# bldc_shield_eagle_layout.net
KiCad netlist of a schematic drawn in EAGLE
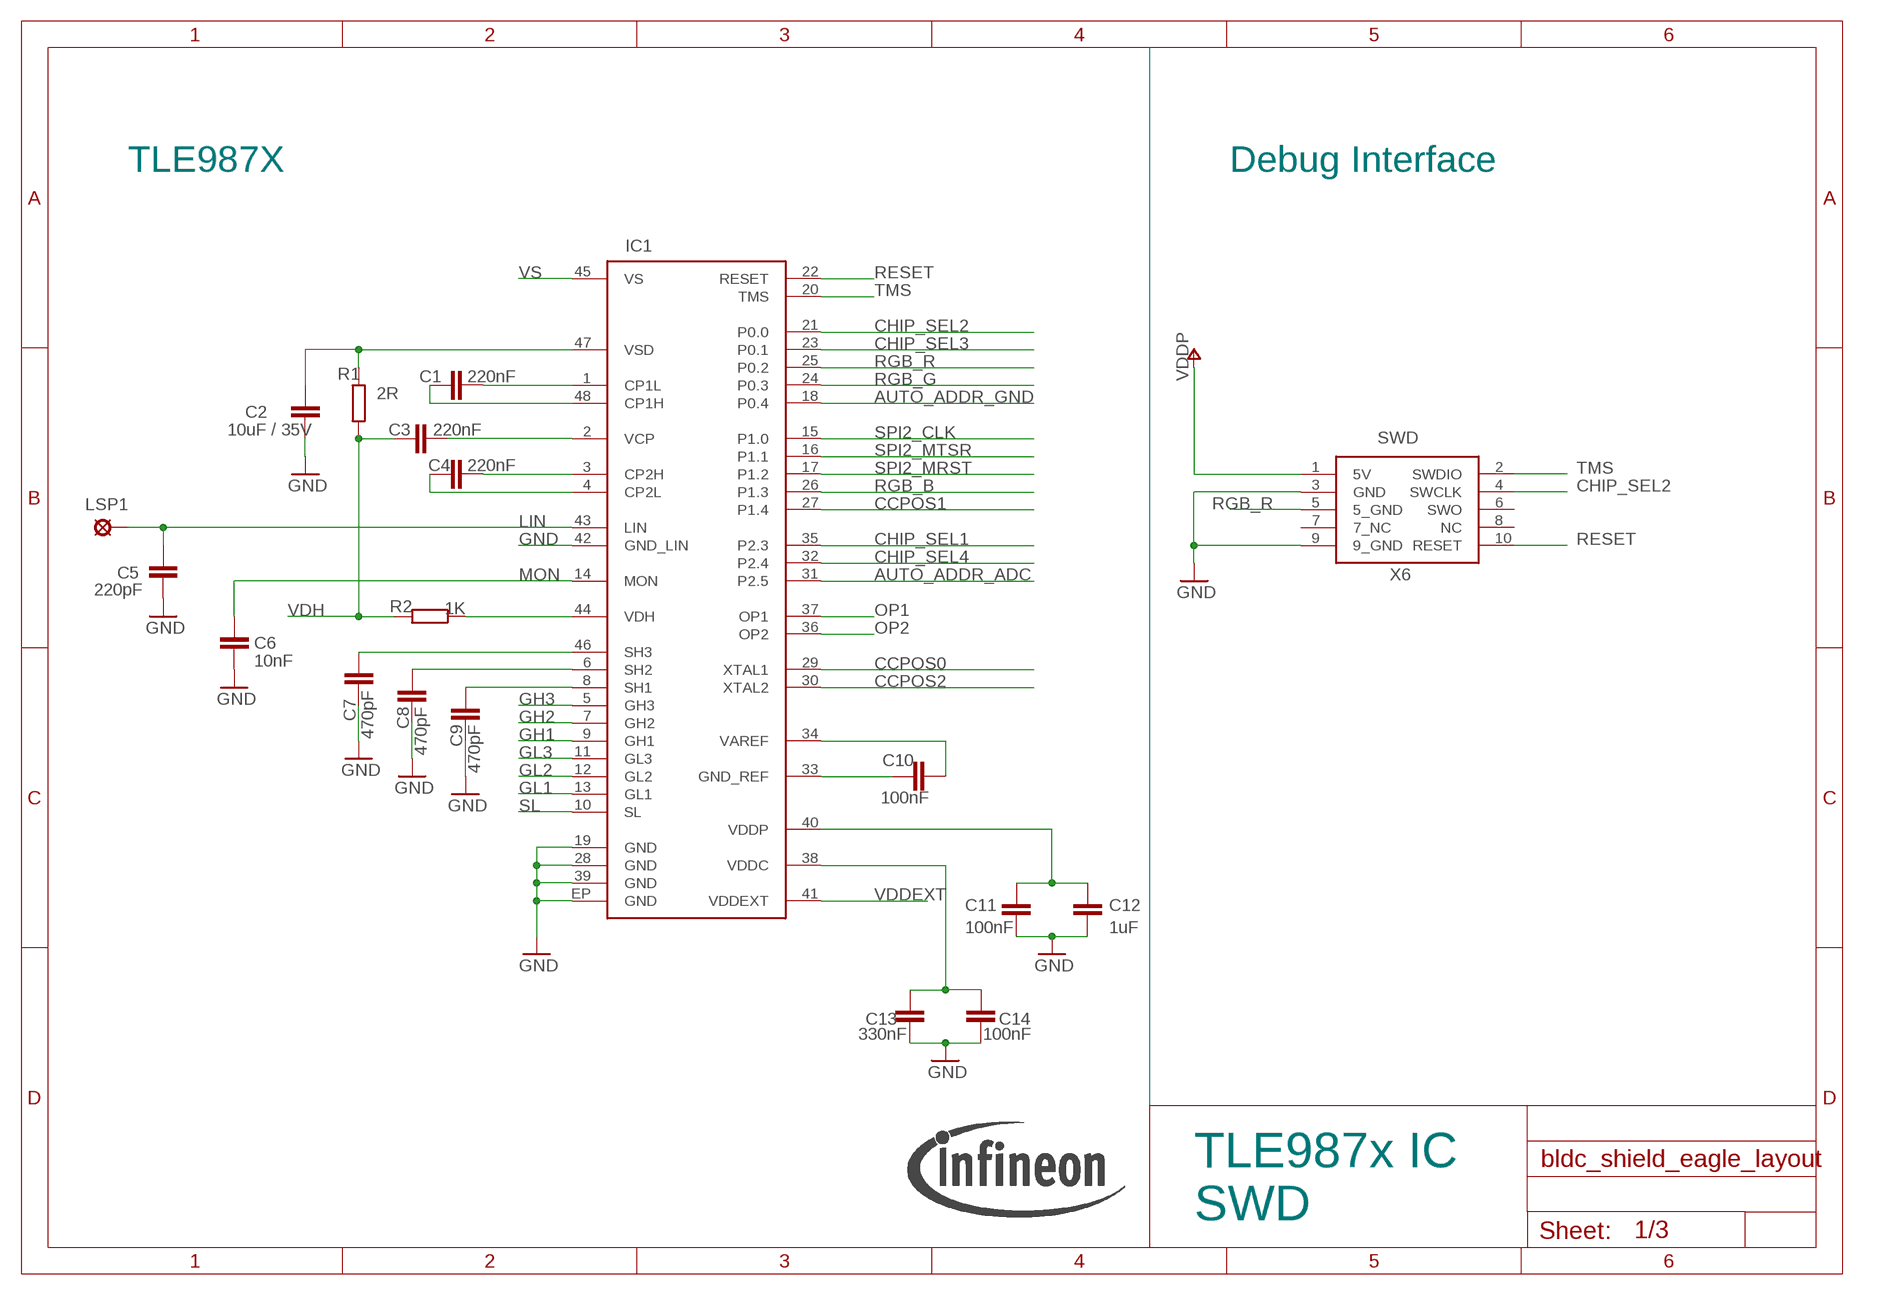
[diagram p0: schematic, sheet 1]
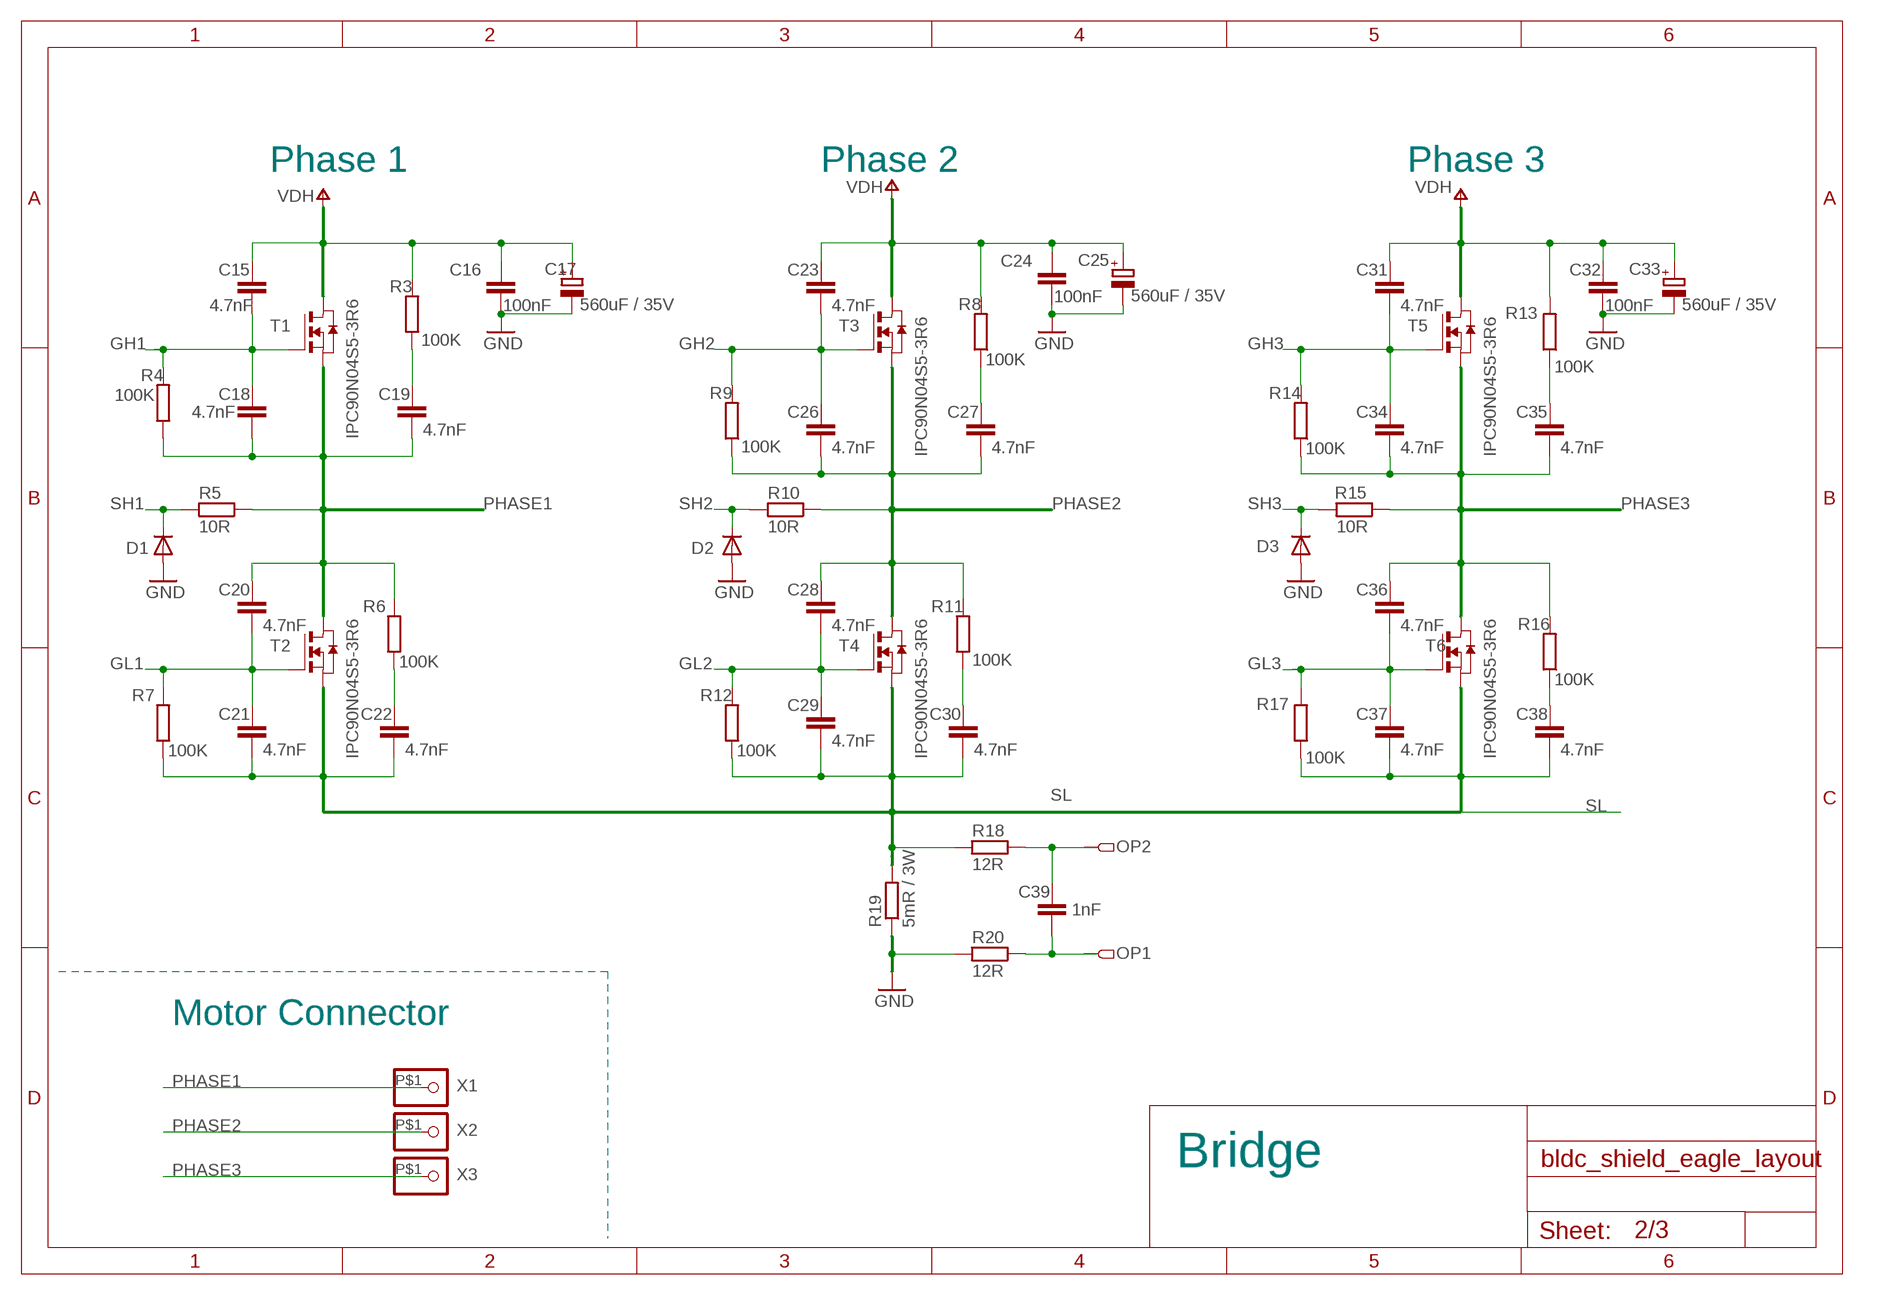
[diagram p1: schematic, sheet 2]
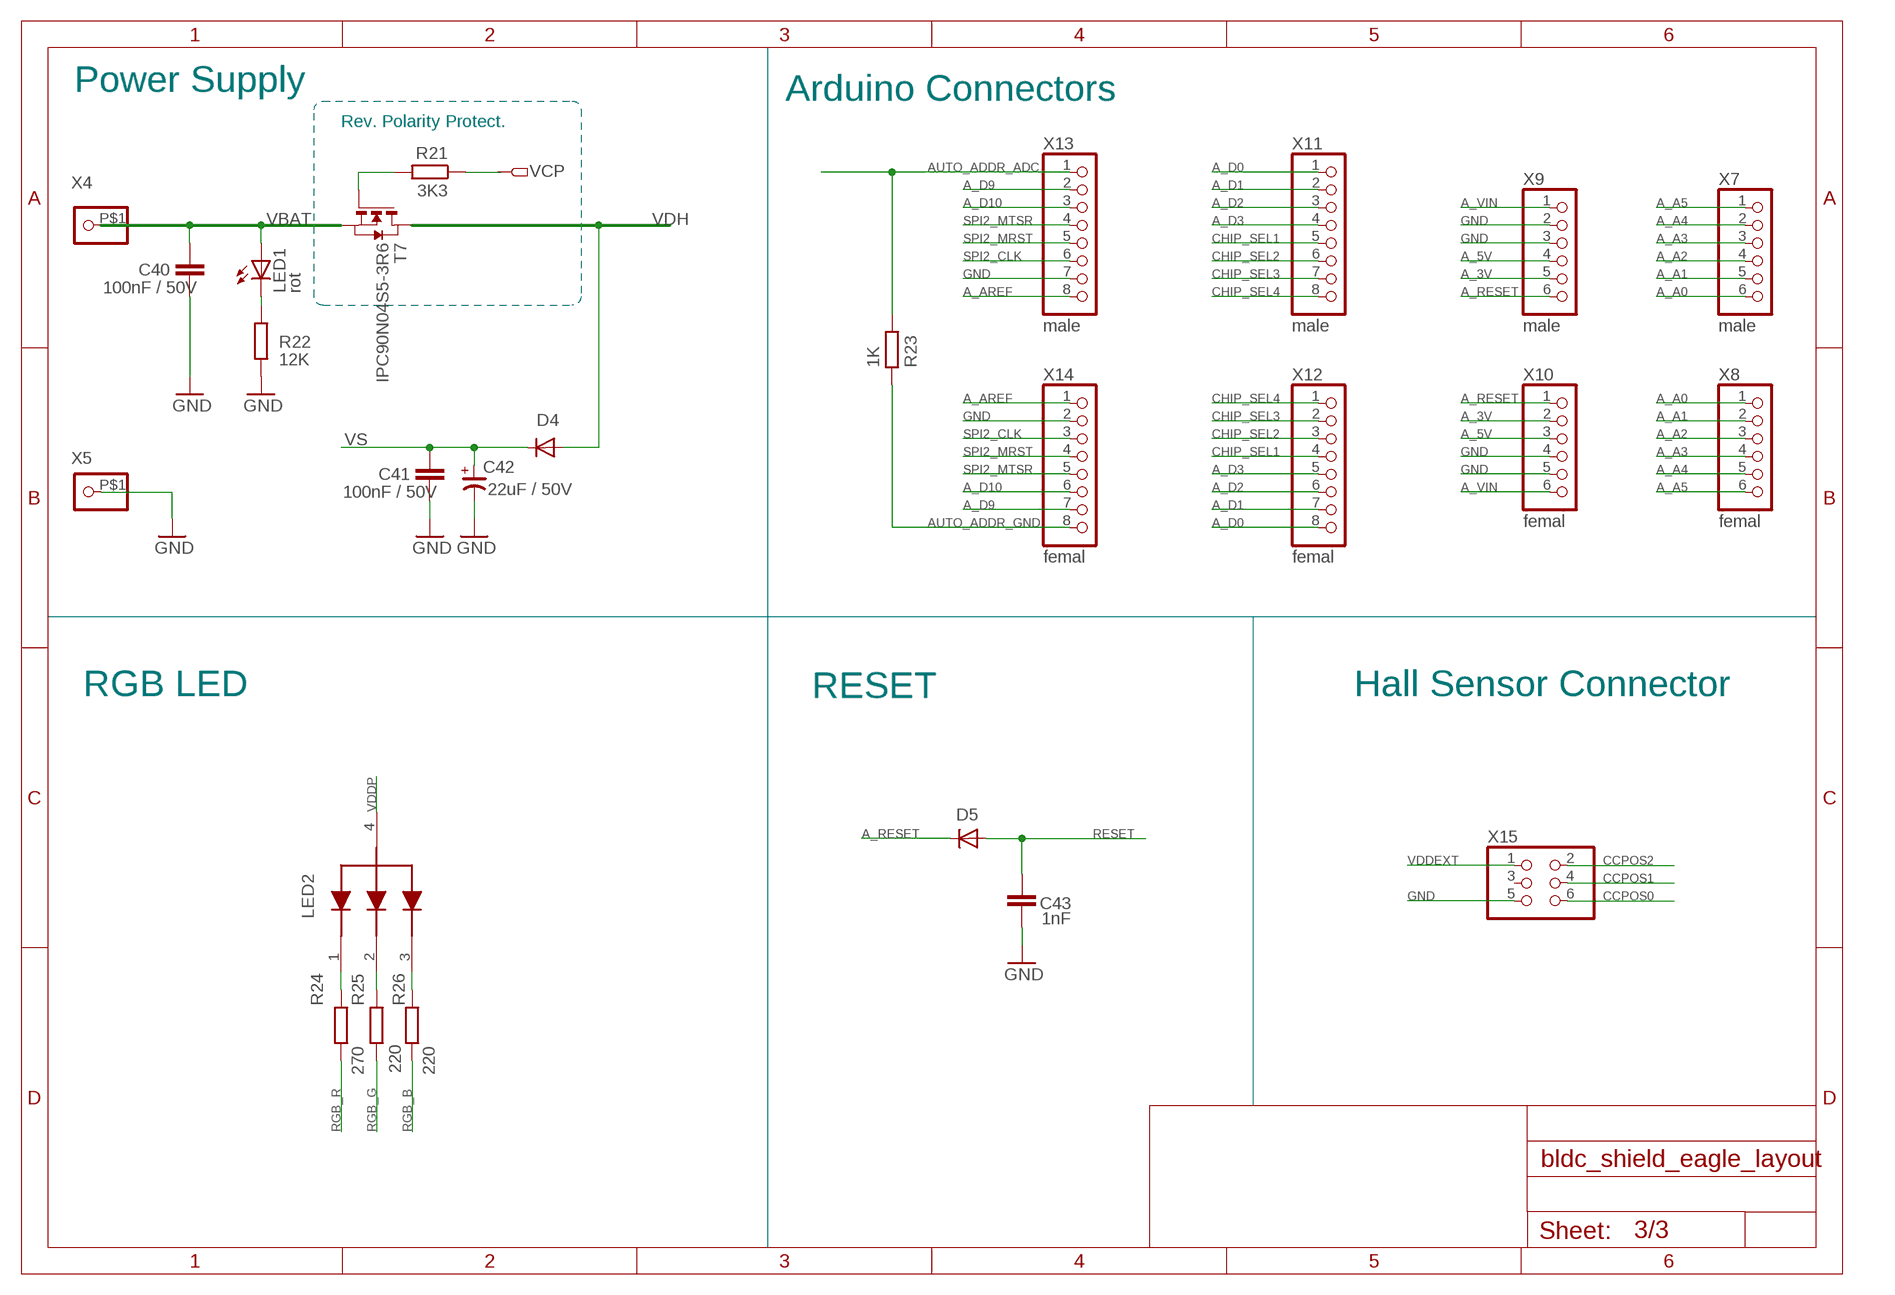
[diagram p2: schematic, sheet 3]

(export (version "E")
  (design (tool "Eeschema 10.0.6"))
  (components
    (comp (ref "C15")
      (value "4.7nF")
      (footprint "eagle-import:C0603")
      (libsource (lib "eagle-import") (part "C-EUC0603"))
    )
    (comp (ref "C16")
      (value "100nF")
      (footprint "eagle-import:C0603")
      (libsource (lib "eagle-import") (part "C-EUC0603"))
    )
    (comp (ref "C17")
      (value "560uF / 35V")
      (footprint "eagle-import:153CLV-1014")
      (libsource (lib "eagle-import") (part "CPOL-EU153CLV-1014"))
    )
    (comp (ref "C18")
      (value "4.7nF")
      (footprint "eagle-import:C0603")
      (libsource (lib "eagle-import") (part "C-EUC0603"))
    )
    (comp (ref "C19")
      (value "4.7nF")
      (footprint "eagle-import:C0603")
      (libsource (lib "eagle-import") (part "C-EUC0603"))
    )
    (comp (ref "C20")
      (value "4.7nF")
      (footprint "eagle-import:C0603")
      (libsource (lib "eagle-import") (part "C-EUC0603"))
    )
    (comp (ref "C21")
      (value "4.7nF")
      (footprint "eagle-import:C0603")
      (libsource (lib "eagle-import") (part "C-EUC0603"))
    )
    (comp (ref "C22")
      (value "4.7nF")
      (footprint "eagle-import:C0603")
      (libsource (lib "eagle-import") (part "C-EUC0603"))
    )
    (comp (ref "C23")
      (value "4.7nF")
      (footprint "eagle-import:C0603")
      (libsource (lib "eagle-import") (part "C-EUC0603"))
    )
    (comp (ref "C24")
      (value "100nF")
      (footprint "eagle-import:C0603")
      (libsource (lib "eagle-import") (part "C-EUC0603"))
    )
    (comp (ref "C25")
      (value "560uF / 35V")
      (footprint "eagle-import:153CLV-1014")
      (libsource (lib "eagle-import") (part "CPOL-EU153CLV-1014"))
    )
    (comp (ref "C26")
      (value "4.7nF")
      (footprint "eagle-import:C0603")
      (libsource (lib "eagle-import") (part "C-EUC0603"))
    )
    (comp (ref "C27")
      (value "4.7nF")
      (footprint "eagle-import:C0603")
      (libsource (lib "eagle-import") (part "C-EUC0603"))
    )
    (comp (ref "C28")
      (value "4.7nF")
      (footprint "eagle-import:C0603")
      (libsource (lib "eagle-import") (part "C-EUC0603"))
    )
    (comp (ref "C29")
      (value "4.7nF")
      (footprint "eagle-import:C0603")
      (libsource (lib "eagle-import") (part "C-EUC0603"))
    )
    (comp (ref "C30")
      (value "4.7nF")
      (footprint "eagle-import:C0603")
      (libsource (lib "eagle-import") (part "C-EUC0603"))
    )
    (comp (ref "C31")
      (value "4.7nF")
      (footprint "eagle-import:C0603")
      (libsource (lib "eagle-import") (part "C-EUC0603"))
    )
    (comp (ref "C32")
      (value "100nF")
      (footprint "eagle-import:C0603")
      (libsource (lib "eagle-import") (part "C-EUC0603"))
    )
    (comp (ref "C33")
      (value "560uF / 35V")
      (footprint "eagle-import:153CLV-1014")
      (libsource (lib "eagle-import") (part "CPOL-EU153CLV-1014"))
    )
    (comp (ref "C34")
      (value "4.7nF")
      (footprint "eagle-import:C0603")
      (libsource (lib "eagle-import") (part "C-EUC0603"))
    )
    (comp (ref "C35")
      (value "4.7nF")
      (footprint "eagle-import:C0603")
      (libsource (lib "eagle-import") (part "C-EUC0603"))
    )
    (comp (ref "C36")
      (value "4.7nF")
      (footprint "eagle-import:C0603")
      (libsource (lib "eagle-import") (part "C-EUC0603"))
    )
    (comp (ref "C37")
      (value "4.7nF")
      (footprint "eagle-import:C0603")
      (libsource (lib "eagle-import") (part "C-EUC0603"))
    )
    (comp (ref "C38")
      (value "4.7nF")
      (footprint "eagle-import:C0603")
      (libsource (lib "eagle-import") (part "C-EUC0603"))
    )
    (comp (ref "C39")
      (value "1nF")
      (footprint "eagle-import:C0603")
      (libsource (lib "eagle-import") (part "C-EUC0603"))
    )
    (comp (ref "D1")
      (value "DIODE-SOD323-W")
      (footprint "eagle-import:SOD323-W")
      (libsource (lib "eagle-import") (part "DIODE-SOD323-W"))
    )
    (comp (ref "D2")
      (value "DIODE-SOD323-W")
      (footprint "eagle-import:SOD323-W")
      (libsource (lib "eagle-import") (part "DIODE-SOD323-W"))
    )
    (comp (ref "D3")
      (value "DIODE-SOD323-W")
      (footprint "eagle-import:SOD323-W")
      (libsource (lib "eagle-import") (part "DIODE-SOD323-W"))
    )
    (comp (ref "R3")
      (value "100K")
      (footprint "eagle-import:R0603")
      (libsource (lib "eagle-import") (part "R-EU_R0603"))
    )
    (comp (ref "R4")
      (value "100K")
      (footprint "eagle-import:R0603")
      (libsource (lib "eagle-import") (part "R-EU_R0603"))
    )
    (comp (ref "R5")
      (value "10R")
      (footprint "eagle-import:R0603")
      (libsource (lib "eagle-import") (part "R-EU_R0603"))
    )
    (comp (ref "R6")
      (value "100K")
      (footprint "eagle-import:R0603")
      (libsource (lib "eagle-import") (part "R-EU_R0603"))
    )
    (comp (ref "R7")
      (value "100K")
      (footprint "eagle-import:R0603")
      (libsource (lib "eagle-import") (part "R-EU_R0603"))
    )
    (comp (ref "R8")
      (value "100K")
      (footprint "eagle-import:R0603")
      (libsource (lib "eagle-import") (part "R-EU_R0603"))
    )
    (comp (ref "R9")
      (value "100K")
      (footprint "eagle-import:R0603")
      (libsource (lib "eagle-import") (part "R-EU_R0603"))
    )
    (comp (ref "R10")
      (value "10R")
      (footprint "eagle-import:R0603")
      (libsource (lib "eagle-import") (part "R-EU_R0603"))
    )
    (comp (ref "R11")
      (value "100K")
      (footprint "eagle-import:R0603")
      (libsource (lib "eagle-import") (part "R-EU_R0603"))
    )
    (comp (ref "R12")
      (value "100K")
      (footprint "eagle-import:R0603")
      (libsource (lib "eagle-import") (part "R-EU_R0603"))
    )
    (comp (ref "R13")
      (value "100K")
      (footprint "eagle-import:R0603")
      (libsource (lib "eagle-import") (part "R-EU_R0603"))
    )
    (comp (ref "R14")
      (value "100K")
      (footprint "eagle-import:R0603")
      (libsource (lib "eagle-import") (part "R-EU_R0603"))
    )
    (comp (ref "R15")
      (value "10R")
      (footprint "eagle-import:R0603")
      (libsource (lib "eagle-import") (part "R-EU_R0603"))
    )
    (comp (ref "R16")
      (value "100K")
      (footprint "eagle-import:R0603")
      (libsource (lib "eagle-import") (part "R-EU_R0603"))
    )
    (comp (ref "R17")
      (value "100K")
      (footprint "eagle-import:R0603")
      (libsource (lib "eagle-import") (part "R-EU_R0603"))
    )
    (comp (ref "R18")
      (value "12R")
      (footprint "eagle-import:R0603")
      (libsource (lib "eagle-import") (part "R-EU_R0603"))
    )
    (comp (ref "R19")
      (value "5mR / 3W")
      (footprint "eagle-import:R6332")
      (libsource (lib "eagle-import") (part "R-EU_R6332"))
    )
    (comp (ref "R20")
      (value "12R")
      (footprint "eagle-import:R0603")
      (libsource (lib "eagle-import") (part "R-EU_R0603"))
    )
    (comp (ref "T1")
      (value "IPC90N04S5-3R6")
      (footprint "eagle-import:PG-TDSON-8")
      (libsource (lib "eagle-import") (part "IPC90N04S5-3R6"))
    )
    (comp (ref "T2")
      (value "IPC90N04S5-3R6")
      (footprint "eagle-import:PG-TDSON-8")
      (libsource (lib "eagle-import") (part "IPC90N04S5-3R6"))
    )
    (comp (ref "T3")
      (value "IPC90N04S5-3R6")
      (footprint "eagle-import:PG-TDSON-8")
      (libsource (lib "eagle-import") (part "IPC90N04S5-3R6"))
    )
    (comp (ref "T4")
      (value "IPC90N04S5-3R6")
      (footprint "eagle-import:PG-TDSON-8")
      (libsource (lib "eagle-import") (part "IPC90N04S5-3R6"))
    )
    (comp (ref "T5")
      (value "IPC90N04S5-3R6")
      (footprint "eagle-import:PG-TDSON-8")
      (libsource (lib "eagle-import") (part "IPC90N04S5-3R6"))
    )
    (comp (ref "T6")
      (value "IPC90N04S5-3R6")
      (footprint "eagle-import:PG-TDSON-8")
      (libsource (lib "eagle-import") (part "IPC90N04S5-3R6"))
    )
    (comp (ref "X1")
      (value "SCREWHOLE")
      (footprint "eagle-import:SCREWHOLE")
      (libsource (lib "eagle-import") (part "SCREWHOLE"))
    )
    (comp (ref "X2")
      (value "SCREWHOLE")
      (footprint "eagle-import:SCREWHOLE")
      (libsource (lib "eagle-import") (part "SCREWHOLE"))
    )
    (comp (ref "X3")
      (value "SCREWHOLE")
      (footprint "eagle-import:SCREWHOLE")
      (libsource (lib "eagle-import") (part "SCREWHOLE"))
    )
    (comp (ref "C40")
      (value "100nF / 50V")
      (footprint "eagle-import:C0603")
      (libsource (lib "eagle-import") (part "C-EUC0603"))
    )
    (comp (ref "C41")
      (value "100nF / 50V")
      (footprint "eagle-import:C0603")
      (libsource (lib "eagle-import") (part "C-EUC0603"))
    )
    (comp (ref "C42")
      (value "22uF / 50V")
      (footprint "eagle-import:153CLV-0505")
      (libsource (lib "eagle-import") (part "CP-153CLV-0505"))
    )
    (comp (ref "C43")
      (value "1nF")
      (footprint "eagle-import:C0603")
      (libsource (lib "eagle-import") (part "C-EUC0603"))
    )
    (comp (ref "D4")
      (value "DIODE_DIODE-SOD123")
      (footprint "eagle-import:DIODE_SOD123")
      (libsource (lib "eagle-import") (part "DIODE_DIODE-SOD123"))
    )
    (comp (ref "D5")
      (value "DIODE-SOD323-W")
      (footprint "eagle-import:SOD323-W")
      (libsource (lib "eagle-import") (part "DIODE-SOD323-W"))
    )
    (comp (ref "LED1")
      (value "rot")
      (footprint "eagle-import:SML0603")
      (libsource (lib "eagle-import") (part "LEDSML0603"))
    )
    (comp (ref "LED2")
      (value "RGB_LED")
      (footprint "eagle-import:LTST-C19HE1WT")
      (libsource (lib "eagle-import") (part "RGB_LED"))
    )
    (comp (ref "R21")
      (value "3K3")
      (footprint "eagle-import:R0603")
      (libsource (lib "eagle-import") (part "R-EU_R0603"))
    )
    (comp (ref "R22")
      (value "12K")
      (footprint "eagle-import:R0603")
      (libsource (lib "eagle-import") (part "R-EU_R0603"))
    )
    (comp (ref "R23")
      (value "1K")
      (footprint "eagle-import:R0603")
      (libsource (lib "eagle-import") (part "R-EU_R0603"))
    )
    (comp (ref "R24")
      (value "270")
      (footprint "eagle-import:R0603")
      (libsource (lib "eagle-import") (part "R-EU_R0603"))
    )
    (comp (ref "R25")
      (value "220")
      (footprint "eagle-import:R0603")
      (libsource (lib "eagle-import") (part "R-EU_R0603"))
    )
    (comp (ref "R26")
      (value "220")
      (footprint "eagle-import:R0603")
      (libsource (lib "eagle-import") (part "R-EU_R0603"))
    )
    (comp (ref "T7")
      (value "IPC90N04S5-3R6")
      (footprint "eagle-import:PG-TDSON-8")
      (libsource (lib "eagle-import") (part "IPC90N04S5-3R6"))
    )
    (comp (ref "X4")
      (value "SCREWHOLE")
      (footprint "eagle-import:SCREWHOLE")
      (libsource (lib "eagle-import") (part "SCREWHOLE"))
    )
    (comp (ref "X5")
      (value "SCREWHOLE")
      (footprint "eagle-import:SCREWHOLE")
      (libsource (lib "eagle-import") (part "SCREWHOLE"))
    )
    (comp (ref "X7")
      (value "male")
      (footprint "eagle-import:1X06SMD")
      (libsource (lib "eagle-import") (part "PINHD-1X6_2.54-SMD"))
    )
    (comp (ref "X8")
      (value "femal")
      (footprint "eagle-import:1X06SMD-FEMAL")
      (libsource (lib "eagle-import") (part "PINHD-1X6_2.54-SMD-FEMAL"))
    )
    (comp (ref "X9")
      (value "male")
      (footprint "eagle-import:1X06SMD")
      (libsource (lib "eagle-import") (part "PINHD-1X6_2.54-SMD"))
    )
    (comp (ref "X10")
      (value "femal")
      (footprint "eagle-import:1X06SMD-FEMAL")
      (libsource (lib "eagle-import") (part "PINHD-1X6_2.54-SMD-FEMAL"))
    )
    (comp (ref "X11")
      (value "male")
      (footprint "eagle-import:1X08SMD")
      (libsource (lib "eagle-import") (part "PINHD-1X8_2.54-SMD"))
    )
    (comp (ref "X12")
      (value "femal")
      (footprint "eagle-import:1X08SMD-FEMAL")
      (libsource (lib "eagle-import") (part "PINHD-1X8_2.54-FEMAL"))
    )
    (comp (ref "X13")
      (value "male")
      (footprint "eagle-import:1X08SMD")
      (libsource (lib "eagle-import") (part "PINHD-1X8_2.54-SMD"))
    )
    (comp (ref "X14")
      (value "femal")
      (footprint "eagle-import:1X08SMD-FEMAL")
      (libsource (lib "eagle-import") (part "PINHD-1X8_2.54-FEMAL"))
    )
    (comp (ref "X15")
      (value "PINHD-2X3_2.54-90°")
      (footprint "eagle-import:2X03_90")
      (libsource (lib "eagle-import") (part "PINHD-2X3_2.54-90°"))
    )
    (comp (ref "C1")
      (value "220nF")
      (footprint "eagle-import:C0603")
      (libsource (lib "eagle-import") (part "C-EUC0603"))
    )
    (comp (ref "C2")
      (value "10uF / 35V")
      (footprint "eagle-import:C1210")
      (libsource (lib "eagle-import") (part "C-EUC1210"))
    )
    (comp (ref "C3")
      (value "220nF")
      (footprint "eagle-import:C0603")
      (libsource (lib "eagle-import") (part "C-EUC0603"))
    )
    (comp (ref "C4")
      (value "220nF")
      (footprint "eagle-import:C0603")
      (libsource (lib "eagle-import") (part "C-EUC0603"))
    )
    (comp (ref "C5")
      (value "220pF")
      (footprint "eagle-import:C0603")
      (libsource (lib "eagle-import") (part "C-EUC0603"))
    )
    (comp (ref "C6")
      (value "10nF")
      (footprint "eagle-import:C0603")
      (libsource (lib "eagle-import") (part "C-EUC0603"))
    )
    (comp (ref "C7")
      (value "470pF")
      (footprint "eagle-import:C0603")
      (libsource (lib "eagle-import") (part "C-EUC0603"))
    )
    (comp (ref "C8")
      (value "470pF")
      (footprint "eagle-import:C0603")
      (libsource (lib "eagle-import") (part "C-EUC0603"))
    )
    (comp (ref "C9")
      (value "470pF")
      (footprint "eagle-import:C0603")
      (libsource (lib "eagle-import") (part "C-EUC0603"))
    )
    (comp (ref "C10")
      (value "100nF")
      (footprint "eagle-import:C0603")
      (libsource (lib "eagle-import") (part "C-EUC0603"))
    )
    (comp (ref "C11")
      (value "100nF")
      (footprint "eagle-import:C0603")
      (libsource (lib "eagle-import") (part "C-EUC0603"))
    )
    (comp (ref "C12")
      (value "1uF")
      (footprint "eagle-import:C0603")
      (libsource (lib "eagle-import") (part "C-EUC0603"))
    )
    (comp (ref "C13")
      (value "330nF")
      (footprint "eagle-import:C0603")
      (libsource (lib "eagle-import") (part "C-EUC0603"))
    )
    (comp (ref "C14")
      (value "100nF")
      (footprint "eagle-import:C0603")
      (libsource (lib "eagle-import") (part "C-EUC0603"))
    )
    (comp (ref "IC1")
      (value "PROTEUS_EAGLE_TLE9879QX")
      (footprint "eagle-import:VQFN48-15_7X7")
      (libsource (lib "eagle-import") (part "PROTEUS_EAGLE_TLE9879QX"))
    )
    (comp (ref "INFINEONLOGO")
      (value "INFINEON5")
      (footprint "eagle-import:INFINEON_LOGO_5")
      (libsource (lib "eagle-import") (part "INFINEON5"))
    )
    (comp (ref "LSP1")
      (value "MCS10B")
      (footprint "eagle-import:MCS10B")
      (libsource (lib "eagle-import") (part "MCS10B"))
    )
    (comp (ref "R1")
      (value "2R")
      (footprint "eagle-import:R0603")
      (libsource (lib "eagle-import") (part "R-EU_R0603"))
    )
    (comp (ref "R2")
      (value "1K")
      (footprint "eagle-import:R0603")
      (libsource (lib "eagle-import") (part "R-EU_R0603"))
    )
    (comp (ref "X6")
      (value "SWD")
      (footprint "eagle-import:FTSH-105-01-L-DH")
      (libsource (lib "eagle-import") (part "SWD"))
    )
  )
  (nets
    (net (code "1") (name "AUTO_ADDR_ADC") (class "Default")
      (node (ref "IC1") (pin "31") (pinfunction "P2.5_31") (pintype "bidirectional"))
      (node (ref "R23") (pin "2") (pinfunction "2_2") (pintype "passive"))
      (node (ref "X13") (pin "1") (pinfunction "1_1") (pintype "passive"))
    )
    (net (code "2") (name "AUTO_ADDR_GND") (class "Default")
      (node (ref "IC1") (pin "18") (pinfunction "P0.4_18") (pintype "bidirectional"))
      (node (ref "R23") (pin "1") (pinfunction "1_1") (pintype "passive"))
      (node (ref "X14") (pin "8") (pinfunction "8_8") (pintype "passive"))
    )
    (net (code "3") (name "A_3V") (class "Default")
      (node (ref "X10") (pin "2") (pinfunction "2_2") (pintype "passive"))
      (node (ref "X9") (pin "5") (pinfunction "5_5") (pintype "passive"))
    )
    (net (code "4") (name "A_5V") (class "Default")
      (node (ref "X10") (pin "3") (pinfunction "3_3") (pintype "passive"))
      (node (ref "X9") (pin "4") (pinfunction "4_4") (pintype "passive"))
    )
    (net (code "5") (name "A_A0") (class "Default")
      (node (ref "X7") (pin "6") (pinfunction "6_6") (pintype "passive"))
      (node (ref "X8") (pin "1") (pinfunction "1_1") (pintype "passive"))
    )
    (net (code "6") (name "A_A1") (class "Default")
      (node (ref "X7") (pin "5") (pinfunction "5_5") (pintype "passive"))
      (node (ref "X8") (pin "2") (pinfunction "2_2") (pintype "passive"))
    )
    (net (code "7") (name "A_A2") (class "Default")
      (node (ref "X7") (pin "4") (pinfunction "4_4") (pintype "passive"))
      (node (ref "X8") (pin "3") (pinfunction "3_3") (pintype "passive"))
    )
    (net (code "8") (name "A_A3") (class "Default")
      (node (ref "X7") (pin "3") (pinfunction "3_3") (pintype "passive"))
      (node (ref "X8") (pin "4") (pinfunction "4_4") (pintype "passive"))
    )
    (net (code "9") (name "A_A4") (class "Default")
      (node (ref "X7") (pin "2") (pinfunction "2_2") (pintype "passive"))
      (node (ref "X8") (pin "5") (pinfunction "5_5") (pintype "passive"))
    )
    (net (code "10") (name "A_A5") (class "Default")
      (node (ref "X7") (pin "1") (pinfunction "1_1") (pintype "passive"))
      (node (ref "X8") (pin "6") (pinfunction "6_6") (pintype "passive"))
    )
    (net (code "11") (name "A_AREF") (class "Default")
      (node (ref "X13") (pin "8") (pinfunction "8_8") (pintype "passive"))
      (node (ref "X14") (pin "1") (pinfunction "1_1") (pintype "passive"))
    )
    (net (code "12") (name "A_D0") (class "Default")
      (node (ref "X11") (pin "1") (pinfunction "1_1") (pintype "passive"))
      (node (ref "X12") (pin "8") (pinfunction "8_8") (pintype "passive"))
    )
    (net (code "13") (name "A_D1") (class "Default")
      (node (ref "X11") (pin "2") (pinfunction "2_2") (pintype "passive"))
      (node (ref "X12") (pin "7") (pinfunction "7_7") (pintype "passive"))
    )
    (net (code "14") (name "A_D2") (class "Default")
      (node (ref "X11") (pin "3") (pinfunction "3_3") (pintype "passive"))
      (node (ref "X12") (pin "6") (pinfunction "6_6") (pintype "passive"))
    )
    (net (code "15") (name "A_D3") (class "Default")
      (node (ref "X11") (pin "4") (pinfunction "4_4") (pintype "passive"))
      (node (ref "X12") (pin "5") (pinfunction "5_5") (pintype "passive"))
    )
    (net (code "16") (name "A_D9") (class "Default")
      (node (ref "X13") (pin "2") (pinfunction "2_2") (pintype "passive"))
      (node (ref "X14") (pin "7") (pinfunction "7_7") (pintype "passive"))
    )
    (net (code "17") (name "A_D10") (class "Default")
      (node (ref "X13") (pin "3") (pinfunction "3_3") (pintype "passive"))
      (node (ref "X14") (pin "6") (pinfunction "6_6") (pintype "passive"))
    )
    (net (code "18") (name "A_RESET") (class "Default")
      (node (ref "D5") (pin "C") (pinfunction "C_C") (pintype "passive"))
      (node (ref "X10") (pin "1") (pinfunction "1_1") (pintype "passive"))
      (node (ref "X9") (pin "6") (pinfunction "6_6") (pintype "passive"))
    )
    (net (code "19") (name "A_VIN") (class "Default")
      (node (ref "X10") (pin "6") (pinfunction "6_6") (pintype "passive"))
      (node (ref "X9") (pin "1") (pinfunction "1_1") (pintype "passive"))
    )
    (net (code "20") (name "CCPOS0") (class "Default")
      (node (ref "IC1") (pin "29") (pinfunction "XTAL1_29") (pintype "passive"))
      (node (ref "X15") (pin "6") (pinfunction "6_6") (pintype "passive"))
    )
    (net (code "21") (name "CCPOS1") (class "Default")
      (node (ref "IC1") (pin "27") (pinfunction "P1.4_27") (pintype "bidirectional"))
      (node (ref "X15") (pin "4") (pinfunction "4_4") (pintype "passive"))
    )
    (net (code "22") (name "CCPOS2") (class "Default")
      (node (ref "IC1") (pin "30") (pinfunction "XTAL2_30") (pintype "passive"))
      (node (ref "X15") (pin "2") (pinfunction "2_2") (pintype "passive"))
    )
    (net (code "23") (name "CHIP_SEL1") (class "Default")
      (node (ref "IC1") (pin "35") (pinfunction "P2.3_35") (pintype "bidirectional"))
      (node (ref "X11") (pin "5") (pinfunction "5_5") (pintype "passive"))
      (node (ref "X12") (pin "4") (pinfunction "4_4") (pintype "passive"))
    )
    (net (code "24") (name "CHIP_SEL2") (class "Default")
      (node (ref "IC1") (pin "21") (pinfunction "P0.0_21") (pintype "bidirectional"))
      (node (ref "X11") (pin "6") (pinfunction "6_6") (pintype "passive"))
      (node (ref "X12") (pin "3") (pinfunction "3_3") (pintype "passive"))
      (node (ref "X6") (pin "4") (pinfunction "SWCLK_4") (pintype "bidirectional"))
    )
    (net (code "25") (name "CHIP_SEL3") (class "Default")
      (node (ref "IC1") (pin "23") (pinfunction "P0.1_23") (pintype "bidirectional"))
      (node (ref "X11") (pin "7") (pinfunction "7_7") (pintype "passive"))
      (node (ref "X12") (pin "2") (pinfunction "2_2") (pintype "passive"))
    )
    (net (code "26") (name "CHIP_SEL4") (class "Default")
      (node (ref "IC1") (pin "32") (pinfunction "P2.4_32") (pintype "bidirectional"))
      (node (ref "X11") (pin "8") (pinfunction "8_8") (pintype "passive"))
      (node (ref "X12") (pin "1") (pinfunction "1_1") (pintype "passive"))
    )
    (net (code "27") (name "GH1") (class "Default")
      (node (ref "C15") (pin "2") (pinfunction "2_2") (pintype "passive"))
      (node (ref "C18") (pin "1") (pinfunction "1_1") (pintype "passive"))
      (node (ref "IC1") (pin "9") (pinfunction "GH1_9") (pintype "passive"))
      (node (ref "R4") (pin "2") (pinfunction "2_2") (pintype "passive"))
      (node (ref "T1") (pin "4") (pinfunction "G_4") (pintype "passive"))
    )
    (net (code "28") (name "GH2") (class "Default")
      (node (ref "C23") (pin "2") (pinfunction "2_2") (pintype "passive"))
      (node (ref "C26") (pin "1") (pinfunction "1_1") (pintype "passive"))
      (node (ref "IC1") (pin "7") (pinfunction "GH2_7") (pintype "passive"))
      (node (ref "R9") (pin "2") (pinfunction "2_2") (pintype "passive"))
      (node (ref "T3") (pin "4") (pinfunction "G_4") (pintype "passive"))
    )
    (net (code "29") (name "GH3") (class "Default")
      (node (ref "C31") (pin "2") (pinfunction "2_2") (pintype "passive"))
      (node (ref "C34") (pin "1") (pinfunction "1_1") (pintype "passive"))
      (node (ref "IC1") (pin "5") (pinfunction "GH3_5") (pintype "passive"))
      (node (ref "R14") (pin "2") (pinfunction "2_2") (pintype "passive"))
      (node (ref "T5") (pin "4") (pinfunction "G_4") (pintype "passive"))
    )
    (net (code "30") (name "GL1") (class "Default")
      (node (ref "C20") (pin "2") (pinfunction "2_2") (pintype "passive"))
      (node (ref "C21") (pin "1") (pinfunction "1_1") (pintype "passive"))
      (node (ref "IC1") (pin "13") (pinfunction "GL1_13") (pintype "passive"))
      (node (ref "R7") (pin "2") (pinfunction "2_2") (pintype "passive"))
      (node (ref "T2") (pin "4") (pinfunction "G_4") (pintype "passive"))
    )
    (net (code "31") (name "GL2") (class "Default")
      (node (ref "C28") (pin "2") (pinfunction "2_2") (pintype "passive"))
      (node (ref "C29") (pin "1") (pinfunction "1_1") (pintype "passive"))
      (node (ref "IC1") (pin "12") (pinfunction "GL2_12") (pintype "passive"))
      (node (ref "R12") (pin "2") (pinfunction "2_2") (pintype "passive"))
      (node (ref "T4") (pin "4") (pinfunction "G_4") (pintype "passive"))
    )
    (net (code "32") (name "GL3") (class "Default")
      (node (ref "C36") (pin "2") (pinfunction "2_2") (pintype "passive"))
      (node (ref "C37") (pin "1") (pinfunction "1_1") (pintype "passive"))
      (node (ref "IC1") (pin "11") (pinfunction "GL3_11") (pintype "passive"))
      (node (ref "R17") (pin "2") (pinfunction "2_2") (pintype "passive"))
      (node (ref "T6") (pin "4") (pinfunction "G_4") (pintype "passive"))
    )
    (net (code "33") (name "GND") (class "Default")
      (node (ref "C11") (pin "1") (pinfunction "1_1") (pintype "passive"))
      (node (ref "C12") (pin "1") (pinfunction "1_1") (pintype "passive"))
      (node (ref "C13") (pin "1") (pinfunction "1_1") (pintype "passive"))
      (node (ref "C14") (pin "1") (pinfunction "1_1") (pintype "passive"))
      (node (ref "C16") (pin "2") (pinfunction "2_2") (pintype "passive"))
      (node (ref "C17") (pin "-") (pinfunction "-_-") (pintype "passive"))
      (node (ref "C2") (pin "2") (pinfunction "2_2") (pintype "passive"))
      (node (ref "C24") (pin "2") (pinfunction "2_2") (pintype "passive"))
      (node (ref "C25") (pin "-") (pinfunction "-_-") (pintype "passive"))
      (node (ref "C32") (pin "2") (pinfunction "2_2") (pintype "passive"))
      (node (ref "C33") (pin "-") (pinfunction "-_-") (pintype "passive"))
      (node (ref "C40") (pin "2") (pinfunction "2_2") (pintype "passive"))
      (node (ref "C41") (pin "2") (pinfunction "2_2") (pintype "passive"))
      (node (ref "C42") (pin "-") (pinfunction "-_-") (pintype "passive"))
      (node (ref "C43") (pin "1") (pinfunction "1_1") (pintype "passive"))
      (node (ref "C5") (pin "1") (pinfunction "1_1") (pintype "passive"))
      (node (ref "C6") (pin "1") (pinfunction "1_1") (pintype "passive"))
      (node (ref "C7") (pin "2") (pinfunction "2_2") (pintype "passive"))
      (node (ref "C8") (pin "1") (pinfunction "1_1") (pintype "passive"))
      (node (ref "C9") (pin "1") (pinfunction "1_1") (pintype "passive"))
      (node (ref "D1") (pin "A") (pinfunction "A_A") (pintype "passive"))
      (node (ref "D2") (pin "A") (pinfunction "A_A") (pintype "passive"))
      (node (ref "D3") (pin "A") (pinfunction "A_A") (pintype "passive"))
      (node (ref "IC1") (pin "19") (pinfunction "GND_19") (pintype "passive"))
      (node (ref "IC1") (pin "28") (pinfunction "GND_28") (pintype "passive"))
      (node (ref "IC1") (pin "39") (pinfunction "GND_39") (pintype "passive"))
      (node (ref "IC1") (pin "42") (pinfunction "GND_LIN_42") (pintype "passive"))
      (node (ref "IC1") (pin "EP") (pinfunction "GND_EP") (pintype "passive"))
      (node (ref "R19") (pin "1") (pinfunction "1_1") (pintype "passive"))
      (node (ref "R20") (pin "2") (pinfunction "2_2") (pintype "passive"))
      (node (ref "R22") (pin "2") (pinfunction "2_2") (pintype "passive"))
      (node (ref "X10") (pin "4") (pinfunction "4_4") (pintype "passive"))
      (node (ref "X10") (pin "5") (pinfunction "5_5") (pintype "passive"))
      (node (ref "X13") (pin "7") (pinfunction "7_7") (pintype "passive"))
      (node (ref "X14") (pin "2") (pinfunction "2_2") (pintype "passive"))
      (node (ref "X15") (pin "5") (pinfunction "5_5") (pintype "passive"))
      (node (ref "X5") (pin "P$1") (pinfunction "1_P$1") (pintype "passive"))
      (node (ref "X6") (pin "3") (pinfunction "GND_3") (pintype "bidirectional"))
      (node (ref "X6") (pin "9") (pinfunction "9_GND_9") (pintype "bidirectional"))
      (node (ref "X9") (pin "2") (pinfunction "2_2") (pintype "passive"))
      (node (ref "X9") (pin "3") (pinfunction "3_3") (pintype "passive"))
    )
    (net (code "34") (name "LIN") (class "Default")
      (node (ref "C5") (pin "2") (pinfunction "2_2") (pintype "passive"))
      (node (ref "IC1") (pin "43") (pinfunction "LIN_43") (pintype "open_collector"))
      (node (ref "LSP1") (pin "MP") (pinfunction "MP_MP") (pintype "passive"))
    )
    (net (code "35") (name "MON") (class "Default")
      (node (ref "C6") (pin "2") (pinfunction "2_2") (pintype "passive"))
      (node (ref "IC1") (pin "14") (pinfunction "MON_14") (pintype "input"))
    )
    (net (code "36") (name "Net-(C19-Pad1)") (class "Default")
      (node (ref "C19") (pin "1") (pinfunction "1_1") (pintype "passive"))
      (node (ref "R3") (pin "1") (pinfunction "1_1") (pintype "passive"))
    )
    (net (code "37") (name "Net-(C22-Pad1)") (class "Default")
      (node (ref "C22") (pin "1") (pinfunction "1_1") (pintype "passive"))
      (node (ref "R6") (pin "1") (pinfunction "1_1") (pintype "passive"))
    )
    (net (code "38") (name "Net-(C27-Pad1)") (class "Default")
      (node (ref "C27") (pin "1") (pinfunction "1_1") (pintype "passive"))
      (node (ref "R8") (pin "1") (pinfunction "1_1") (pintype "passive"))
    )
    (net (code "39") (name "Net-(C30-Pad1)") (class "Default")
      (node (ref "C30") (pin "1") (pinfunction "1_1") (pintype "passive"))
      (node (ref "R11") (pin "1") (pinfunction "1_1") (pintype "passive"))
    )
    (net (code "40") (name "Net-(C35-Pad1)") (class "Default")
      (node (ref "C35") (pin "1") (pinfunction "1_1") (pintype "passive"))
      (node (ref "R13") (pin "1") (pinfunction "1_1") (pintype "passive"))
    )
    (net (code "41") (name "Net-(C38-Pad1)") (class "Default")
      (node (ref "C38") (pin "1") (pinfunction "1_1") (pintype "passive"))
      (node (ref "R16") (pin "1") (pinfunction "1_1") (pintype "passive"))
    )
    (net (code "42") (name "Net-(IC1-CP1H)") (class "Default")
      (node (ref "C1") (pin "2") (pinfunction "2_2") (pintype "passive"))
      (node (ref "IC1") (pin "48") (pinfunction "CP1H_48") (pintype "passive"))
    )
    (net (code "43") (name "Net-(IC1-CP1L)") (class "Default")
      (node (ref "C1") (pin "1") (pinfunction "1_1") (pintype "passive"))
      (node (ref "IC1") (pin "1") (pinfunction "CP1L_1") (pintype "passive"))
    )
    (net (code "44") (name "Net-(IC1-CP2H)") (class "Default")
      (node (ref "C4") (pin "1") (pinfunction "1_1") (pintype "passive"))
      (node (ref "IC1") (pin "3") (pinfunction "CP2H_3") (pintype "passive"))
    )
    (net (code "45") (name "Net-(IC1-CP2L)") (class "Default")
      (node (ref "C4") (pin "2") (pinfunction "2_2") (pintype "passive"))
      (node (ref "IC1") (pin "4") (pinfunction "CP2L_4") (pintype "passive"))
    )
    (net (code "46") (name "Net-(IC1-GND_REF)") (class "Default")
      (node (ref "C10") (pin "1") (pinfunction "1_1") (pintype "passive"))
      (node (ref "IC1") (pin "33") (pinfunction "GND_REF_33") (pintype "passive"))
    )
    (net (code "47") (name "Net-(IC1-VAREF)") (class "Default")
      (node (ref "C10") (pin "2") (pinfunction "2_2") (pintype "passive"))
      (node (ref "IC1") (pin "34") (pinfunction "VAREF_34") (pintype "passive"))
    )
    (net (code "48") (name "Net-(IC1-VDDC)") (class "Default")
      (node (ref "C13") (pin "2") (pinfunction "2_2") (pintype "passive"))
      (node (ref "C14") (pin "2") (pinfunction "2_2") (pintype "passive"))
      (node (ref "IC1") (pin "38") (pinfunction "VDDC_38") (pintype "passive"))
    )
    (net (code "49") (name "Net-(IC1-VDH)") (class "Default")
      (node (ref "IC1") (pin "44") (pinfunction "VDH_44") (pintype "passive"))
      (node (ref "R2") (pin "1") (pinfunction "1_1") (pintype "passive"))
    )
    (net (code "50") (name "Net-(IC1-VSD)") (class "Default")
      (node (ref "C2") (pin "1") (pinfunction "1_1") (pintype "passive"))
      (node (ref "IC1") (pin "47") (pinfunction "VSD_47") (pintype "passive"))
      (node (ref "R1") (pin "1") (pinfunction "1_1") (pintype "passive"))
    )
    (net (code "51") (name "Net-(LED1-PadC)") (class "Default")
      (node (ref "LED1") (pin "C") (pinfunction "C_C") (pintype "passive"))
      (node (ref "R22") (pin "1") (pinfunction "1_1") (pintype "passive"))
    )
    (net (code "52") (name "Net-(LED2-Pad1)") (class "Default")
      (node (ref "LED2") (pin "1") (pinfunction "1_1") (pintype "bidirectional"))
      (node (ref "R24") (pin "1") (pinfunction "1_1") (pintype "passive"))
    )
    (net (code "53") (name "Net-(LED2-Pad2)") (class "Default")
      (node (ref "LED2") (pin "2") (pinfunction "2_2") (pintype "bidirectional"))
      (node (ref "R25") (pin "1") (pinfunction "1_1") (pintype "passive"))
    )
    (net (code "54") (name "Net-(LED2-Pad3)") (class "Default")
      (node (ref "LED2") (pin "3") (pinfunction "3_3") (pintype "bidirectional"))
      (node (ref "R26") (pin "1") (pinfunction "1_1") (pintype "passive"))
    )
    (net (code "55") (name "Net-(T7-G)") (class "Default")
      (node (ref "R21") (pin "2") (pinfunction "2_2") (pintype "passive"))
      (node (ref "T7") (pin "4") (pinfunction "G_4") (pintype "passive"))
    )
    (net (code "56") (name "OP1") (class "Default")
      (node (ref "C39") (pin "2") (pinfunction "2_2") (pintype "passive"))
      (node (ref "IC1") (pin "37") (pinfunction "OP1_37") (pintype "passive"))
      (node (ref "R20") (pin "1") (pinfunction "1_1") (pintype "passive"))
    )
    (net (code "57") (name "OP2") (class "Default")
      (node (ref "C39") (pin "1") (pinfunction "1_1") (pintype "passive"))
      (node (ref "IC1") (pin "36") (pinfunction "OP2_36") (pintype "passive"))
      (node (ref "R18") (pin "1") (pinfunction "1_1") (pintype "passive"))
    )
    (net (code "58") (name "PHASE1") (class "Default")
      (node (ref "C18") (pin "2") (pinfunction "2_2") (pintype "passive"))
      (node (ref "C19") (pin "2") (pinfunction "2_2") (pintype "passive"))
      (node (ref "C20") (pin "1") (pinfunction "1_1") (pintype "passive"))
      (node (ref "R4") (pin "1") (pinfunction "1_1") (pintype "passive"))
      (node (ref "R5") (pin "1") (pinfunction "1_1") (pintype "passive"))
      (node (ref "R6") (pin "2") (pinfunction "2_2") (pintype "passive"))
      (node (ref "T1") (pin "1") (pinfunction "S_1") (pintype "passive"))
      (node (ref "T1") (pin "2") (pinfunction "S_2") (pintype "passive"))
      (node (ref "T1") (pin "3") (pinfunction "S_3") (pintype "passive"))
      (node (ref "T2") (pin "5") (pinfunction "D_5") (pintype "passive"))
      (node (ref "T2") (pin "6") (pinfunction "D_6") (pintype "passive"))
      (node (ref "T2") (pin "7") (pinfunction "D_7") (pintype "passive"))
      (node (ref "T2") (pin "8") (pinfunction "D_8") (pintype "passive"))
      (node (ref "T2") (pin "D") (pinfunction "D_D") (pintype "passive"))
      (node (ref "X1") (pin "P$1") (pinfunction "1_P$1") (pintype "passive"))
    )
    (net (code "59") (name "PHASE2") (class "Default")
      (node (ref "C26") (pin "2") (pinfunction "2_2") (pintype "passive"))
      (node (ref "C27") (pin "2") (pinfunction "2_2") (pintype "passive"))
      (node (ref "C28") (pin "1") (pinfunction "1_1") (pintype "passive"))
      (node (ref "R10") (pin "1") (pinfunction "1_1") (pintype "passive"))
      (node (ref "R11") (pin "2") (pinfunction "2_2") (pintype "passive"))
      (node (ref "R9") (pin "1") (pinfunction "1_1") (pintype "passive"))
      (node (ref "T3") (pin "1") (pinfunction "S_1") (pintype "passive"))
      (node (ref "T3") (pin "2") (pinfunction "S_2") (pintype "passive"))
      (node (ref "T3") (pin "3") (pinfunction "S_3") (pintype "passive"))
      (node (ref "T4") (pin "5") (pinfunction "D_5") (pintype "passive"))
      (node (ref "T4") (pin "6") (pinfunction "D_6") (pintype "passive"))
      (node (ref "T4") (pin "7") (pinfunction "D_7") (pintype "passive"))
      (node (ref "T4") (pin "8") (pinfunction "D_8") (pintype "passive"))
      (node (ref "T4") (pin "D") (pinfunction "D_D") (pintype "passive"))
      (node (ref "X2") (pin "P$1") (pinfunction "1_P$1") (pintype "passive"))
    )
    (net (code "60") (name "PHASE3") (class "Default")
      (node (ref "C34") (pin "2") (pinfunction "2_2") (pintype "passive"))
      (node (ref "C35") (pin "2") (pinfunction "2_2") (pintype "passive"))
      (node (ref "C36") (pin "1") (pinfunction "1_1") (pintype "passive"))
      (node (ref "R14") (pin "1") (pinfunction "1_1") (pintype "passive"))
      (node (ref "R15") (pin "1") (pinfunction "1_1") (pintype "passive"))
      (node (ref "R16") (pin "2") (pinfunction "2_2") (pintype "passive"))
      (node (ref "T5") (pin "1") (pinfunction "S_1") (pintype "passive"))
      (node (ref "T5") (pin "2") (pinfunction "S_2") (pintype "passive"))
      (node (ref "T5") (pin "3") (pinfunction "S_3") (pintype "passive"))
      (node (ref "T6") (pin "5") (pinfunction "D_5") (pintype "passive"))
      (node (ref "T6") (pin "6") (pinfunction "D_6") (pintype "passive"))
      (node (ref "T6") (pin "7") (pinfunction "D_7") (pintype "passive"))
      (node (ref "T6") (pin "8") (pinfunction "D_8") (pintype "passive"))
      (node (ref "T6") (pin "D") (pinfunction "D_D") (pintype "passive"))
      (node (ref "X3") (pin "P$1") (pinfunction "1_P$1") (pintype "passive"))
    )
    (net (code "61") (name "RESET") (class "Default")
      (node (ref "C43") (pin "2") (pinfunction "2_2") (pintype "passive"))
      (node (ref "D5") (pin "A") (pinfunction "A_A") (pintype "passive"))
      (node (ref "IC1") (pin "22") (pinfunction "RESET_22") (pintype "bidirectional"))
      (node (ref "X6") (pin "10") (pinfunction "RESET_10") (pintype "bidirectional"))
    )
    (net (code "62") (name "RGB_B") (class "Default")
      (node (ref "IC1") (pin "26") (pinfunction "P1.3_26") (pintype "bidirectional"))
      (node (ref "R26") (pin "2") (pinfunction "2_2") (pintype "passive"))
    )
    (net (code "63") (name "RGB_G") (class "Default")
      (node (ref "IC1") (pin "24") (pinfunction "P0.3_24") (pintype "bidirectional"))
      (node (ref "R25") (pin "2") (pinfunction "2_2") (pintype "passive"))
    )
    (net (code "64") (name "RGB_R") (class "Default")
      (node (ref "IC1") (pin "25") (pinfunction "P0.2_25") (pintype "bidirectional"))
      (node (ref "R24") (pin "2") (pinfunction "2_2") (pintype "passive"))
      (node (ref "X6") (pin "5") (pinfunction "5_GND_5") (pintype "bidirectional"))
    )
    (net (code "65") (name "SH1") (class "Default")
      (node (ref "C9") (pin "2") (pinfunction "2_2") (pintype "passive"))
      (node (ref "D1") (pin "C") (pinfunction "C_C") (pintype "passive"))
      (node (ref "IC1") (pin "8") (pinfunction "SH1_8") (pintype "passive"))
      (node (ref "R5") (pin "2") (pinfunction "2_2") (pintype "passive"))
    )
    (net (code "66") (name "SH2") (class "Default")
      (node (ref "C8") (pin "2") (pinfunction "2_2") (pintype "passive"))
      (node (ref "D2") (pin "C") (pinfunction "C_C") (pintype "passive"))
      (node (ref "IC1") (pin "6") (pinfunction "SH2_6") (pintype "passive"))
      (node (ref "R10") (pin "2") (pinfunction "2_2") (pintype "passive"))
    )
    (net (code "67") (name "SH3") (class "Default")
      (node (ref "C7") (pin "1") (pinfunction "1_1") (pintype "passive"))
      (node (ref "D3") (pin "C") (pinfunction "C_C") (pintype "passive"))
      (node (ref "IC1") (pin "46") (pinfunction "SH3_46") (pintype "passive"))
      (node (ref "R15") (pin "2") (pinfunction "2_2") (pintype "passive"))
    )
    (net (code "68") (name "SL") (class "Default")
      (node (ref "C21") (pin "2") (pinfunction "2_2") (pintype "passive"))
      (node (ref "C22") (pin "2") (pinfunction "2_2") (pintype "passive"))
      (node (ref "C29") (pin "2") (pinfunction "2_2") (pintype "passive"))
      (node (ref "C30") (pin "2") (pinfunction "2_2") (pintype "passive"))
      (node (ref "C37") (pin "2") (pinfunction "2_2") (pintype "passive"))
      (node (ref "C38") (pin "2") (pinfunction "2_2") (pintype "passive"))
      (node (ref "IC1") (pin "10") (pinfunction "SL_10") (pintype "passive"))
      (node (ref "R12") (pin "1") (pinfunction "1_1") (pintype "passive"))
      (node (ref "R17") (pin "1") (pinfunction "1_1") (pintype "passive"))
      (node (ref "R18") (pin "2") (pinfunction "2_2") (pintype "passive"))
      (node (ref "R19") (pin "2") (pinfunction "2_2") (pintype "passive"))
      (node (ref "R7") (pin "1") (pinfunction "1_1") (pintype "passive"))
      (node (ref "T2") (pin "1") (pinfunction "S_1") (pintype "passive"))
      (node (ref "T2") (pin "2") (pinfunction "S_2") (pintype "passive"))
      (node (ref "T2") (pin "3") (pinfunction "S_3") (pintype "passive"))
      (node (ref "T4") (pin "1") (pinfunction "S_1") (pintype "passive"))
      (node (ref "T4") (pin "2") (pinfunction "S_2") (pintype "passive"))
      (node (ref "T4") (pin "3") (pinfunction "S_3") (pintype "passive"))
      (node (ref "T6") (pin "1") (pinfunction "S_1") (pintype "passive"))
      (node (ref "T6") (pin "2") (pinfunction "S_2") (pintype "passive"))
      (node (ref "T6") (pin "3") (pinfunction "S_3") (pintype "passive"))
    )
    (net (code "69") (name "SPI2_CLK") (class "Default")
      (node (ref "IC1") (pin "15") (pinfunction "P1.0_15") (pintype "bidirectional"))
      (node (ref "X13") (pin "6") (pinfunction "6_6") (pintype "passive"))
      (node (ref "X14") (pin "3") (pinfunction "3_3") (pintype "passive"))
    )
    (net (code "70") (name "SPI2_MRST") (class "Default")
      (node (ref "IC1") (pin "17") (pinfunction "P1.2_17") (pintype "bidirectional"))
      (node (ref "X13") (pin "5") (pinfunction "5_5") (pintype "passive"))
      (node (ref "X14") (pin "4") (pinfunction "4_4") (pintype "passive"))
    )
    (net (code "71") (name "SPI2_MTSR") (class "Default")
      (node (ref "IC1") (pin "16") (pinfunction "P1.1_16") (pintype "bidirectional"))
      (node (ref "X13") (pin "4") (pinfunction "4_4") (pintype "passive"))
      (node (ref "X14") (pin "5") (pinfunction "5_5") (pintype "passive"))
    )
    (net (code "72") (name "TMS") (class "Default")
      (node (ref "IC1") (pin "20") (pinfunction "TMS_20") (pintype "input"))
      (node (ref "X6") (pin "2") (pinfunction "SWDIO_2") (pintype "bidirectional"))
    )
    (net (code "73") (name "VBAT") (class "Default")
      (node (ref "C40") (pin "1") (pinfunction "1_1") (pintype "passive"))
      (node (ref "LED1") (pin "A") (pinfunction "A_A") (pintype "passive"))
      (node (ref "T7") (pin "1") (pinfunction "S_1") (pintype "passive"))
      (node (ref "T7") (pin "2") (pinfunction "S_2") (pintype "passive"))
      (node (ref "T7") (pin "3") (pinfunction "S_3") (pintype "passive"))
      (node (ref "X4") (pin "P$1") (pinfunction "1_P$1") (pintype "passive"))
    )
    (net (code "74") (name "VCP") (class "Default")
      (node (ref "C3") (pin "1") (pinfunction "1_1") (pintype "passive"))
      (node (ref "IC1") (pin "2") (pinfunction "VCP_2") (pintype "passive"))
      (node (ref "R21") (pin "1") (pinfunction "1_1") (pintype "passive"))
    )
    (net (code "75") (name "VDDEXT") (class "Default")
      (node (ref "IC1") (pin "41") (pinfunction "VDDEXT_41") (pintype "passive"))
      (node (ref "X15") (pin "1") (pinfunction "1_1") (pintype "passive"))
    )
    (net (code "76") (name "VDDP") (class "Default")
      (node (ref "C11") (pin "2") (pinfunction "2_2") (pintype "passive"))
      (node (ref "C12") (pin "2") (pinfunction "2_2") (pintype "passive"))
      (node (ref "IC1") (pin "40") (pinfunction "VDDP_40") (pintype "passive"))
      (node (ref "LED2") (pin "4") (pinfunction "4_4") (pintype "bidirectional"))
      (node (ref "X6") (pin "1") (pinfunction "5V_1") (pintype "power_in"))
    )
    (net (code "77") (name "VDH") (class "Default")
      (node (ref "C15") (pin "1") (pinfunction "1_1") (pintype "passive"))
      (node (ref "C16") (pin "1") (pinfunction "1_1") (pintype "passive"))
      (node (ref "C17") (pin "+") (pinfunction "+_+") (pintype "passive"))
      (node (ref "C23") (pin "1") (pinfunction "1_1") (pintype "passive"))
      (node (ref "C24") (pin "1") (pinfunction "1_1") (pintype "passive"))
      (node (ref "C25") (pin "+") (pinfunction "+_+") (pintype "passive"))
      (node (ref "C3") (pin "2") (pinfunction "2_2") (pintype "passive"))
      (node (ref "C31") (pin "1") (pinfunction "1_1") (pintype "passive"))
      (node (ref "C32") (pin "1") (pinfunction "1_1") (pintype "passive"))
      (node (ref "C33") (pin "+") (pinfunction "+_+") (pintype "passive"))
      (node (ref "D4") (pin "A") (pinfunction "A_A") (pintype "passive"))
      (node (ref "R1") (pin "2") (pinfunction "2_2") (pintype "passive"))
      (node (ref "R13") (pin "2") (pinfunction "2_2") (pintype "passive"))
      (node (ref "R2") (pin "2") (pinfunction "2_2") (pintype "passive"))
      (node (ref "R3") (pin "2") (pinfunction "2_2") (pintype "passive"))
      (node (ref "R8") (pin "2") (pinfunction "2_2") (pintype "passive"))
      (node (ref "T1") (pin "5") (pinfunction "D_5") (pintype "passive"))
      (node (ref "T1") (pin "6") (pinfunction "D_6") (pintype "passive"))
      (node (ref "T1") (pin "7") (pinfunction "D_7") (pintype "passive"))
      (node (ref "T1") (pin "8") (pinfunction "D_8") (pintype "passive"))
      (node (ref "T1") (pin "D") (pinfunction "D_D") (pintype "passive"))
      (node (ref "T3") (pin "5") (pinfunction "D_5") (pintype "passive"))
      (node (ref "T3") (pin "6") (pinfunction "D_6") (pintype "passive"))
      (node (ref "T3") (pin "7") (pinfunction "D_7") (pintype "passive"))
      (node (ref "T3") (pin "8") (pinfunction "D_8") (pintype "passive"))
      (node (ref "T3") (pin "D") (pinfunction "D_D") (pintype "passive"))
      (node (ref "T5") (pin "5") (pinfunction "D_5") (pintype "passive"))
      (node (ref "T5") (pin "6") (pinfunction "D_6") (pintype "passive"))
      (node (ref "T5") (pin "7") (pinfunction "D_7") (pintype "passive"))
      (node (ref "T5") (pin "8") (pinfunction "D_8") (pintype "passive"))
      (node (ref "T5") (pin "D") (pinfunction "D_D") (pintype "passive"))
      (node (ref "T7") (pin "5") (pinfunction "D_5") (pintype "passive"))
      (node (ref "T7") (pin "6") (pinfunction "D_6") (pintype "passive"))
      (node (ref "T7") (pin "7") (pinfunction "D_7") (pintype "passive"))
      (node (ref "T7") (pin "8") (pinfunction "D_8") (pintype "passive"))
      (node (ref "T7") (pin "D") (pinfunction "D_D") (pintype "passive"))
    )
    (net (code "78") (name "VS") (class "Default")
      (node (ref "C41") (pin "1") (pinfunction "1_1") (pintype "passive"))
      (node (ref "C42") (pin "+") (pinfunction "+_+") (pintype "passive"))
      (node (ref "D4") (pin "C") (pinfunction "C_C") (pintype "passive"))
      (node (ref "IC1") (pin "45") (pinfunction "VS_45") (pintype "passive"))
    )
    (net (code "79") (name "unconnected-(X6-7_NC-Pad7)") (class "Default")
      (node (ref "X6") (pin "7") (pinfunction "7_NC_7") (pintype "no_connect"))
    )
    (net (code "80") (name "unconnected-(X6-NC-Pad8)") (class "Default")
      (node (ref "X6") (pin "8") (pinfunction "NC_8") (pintype "no_connect"))
    )
    (net (code "81") (name "unconnected-(X6-SWO-Pad6)") (class "Default")
      (node (ref "X6") (pin "6") (pinfunction "SWO_6") (pintype "bidirectional"))
    )
    (net (code "82") (name "unconnected-(X15-Pad3)") (class "Default")
      (node (ref "X15") (pin "3") (pinfunction "3_3") (pintype "passive"))
    )
  )
)
